# P-LED-0005-V1A_EAGLE_Schematic.net
KiCad netlist of a schematic drawn in EAGLE
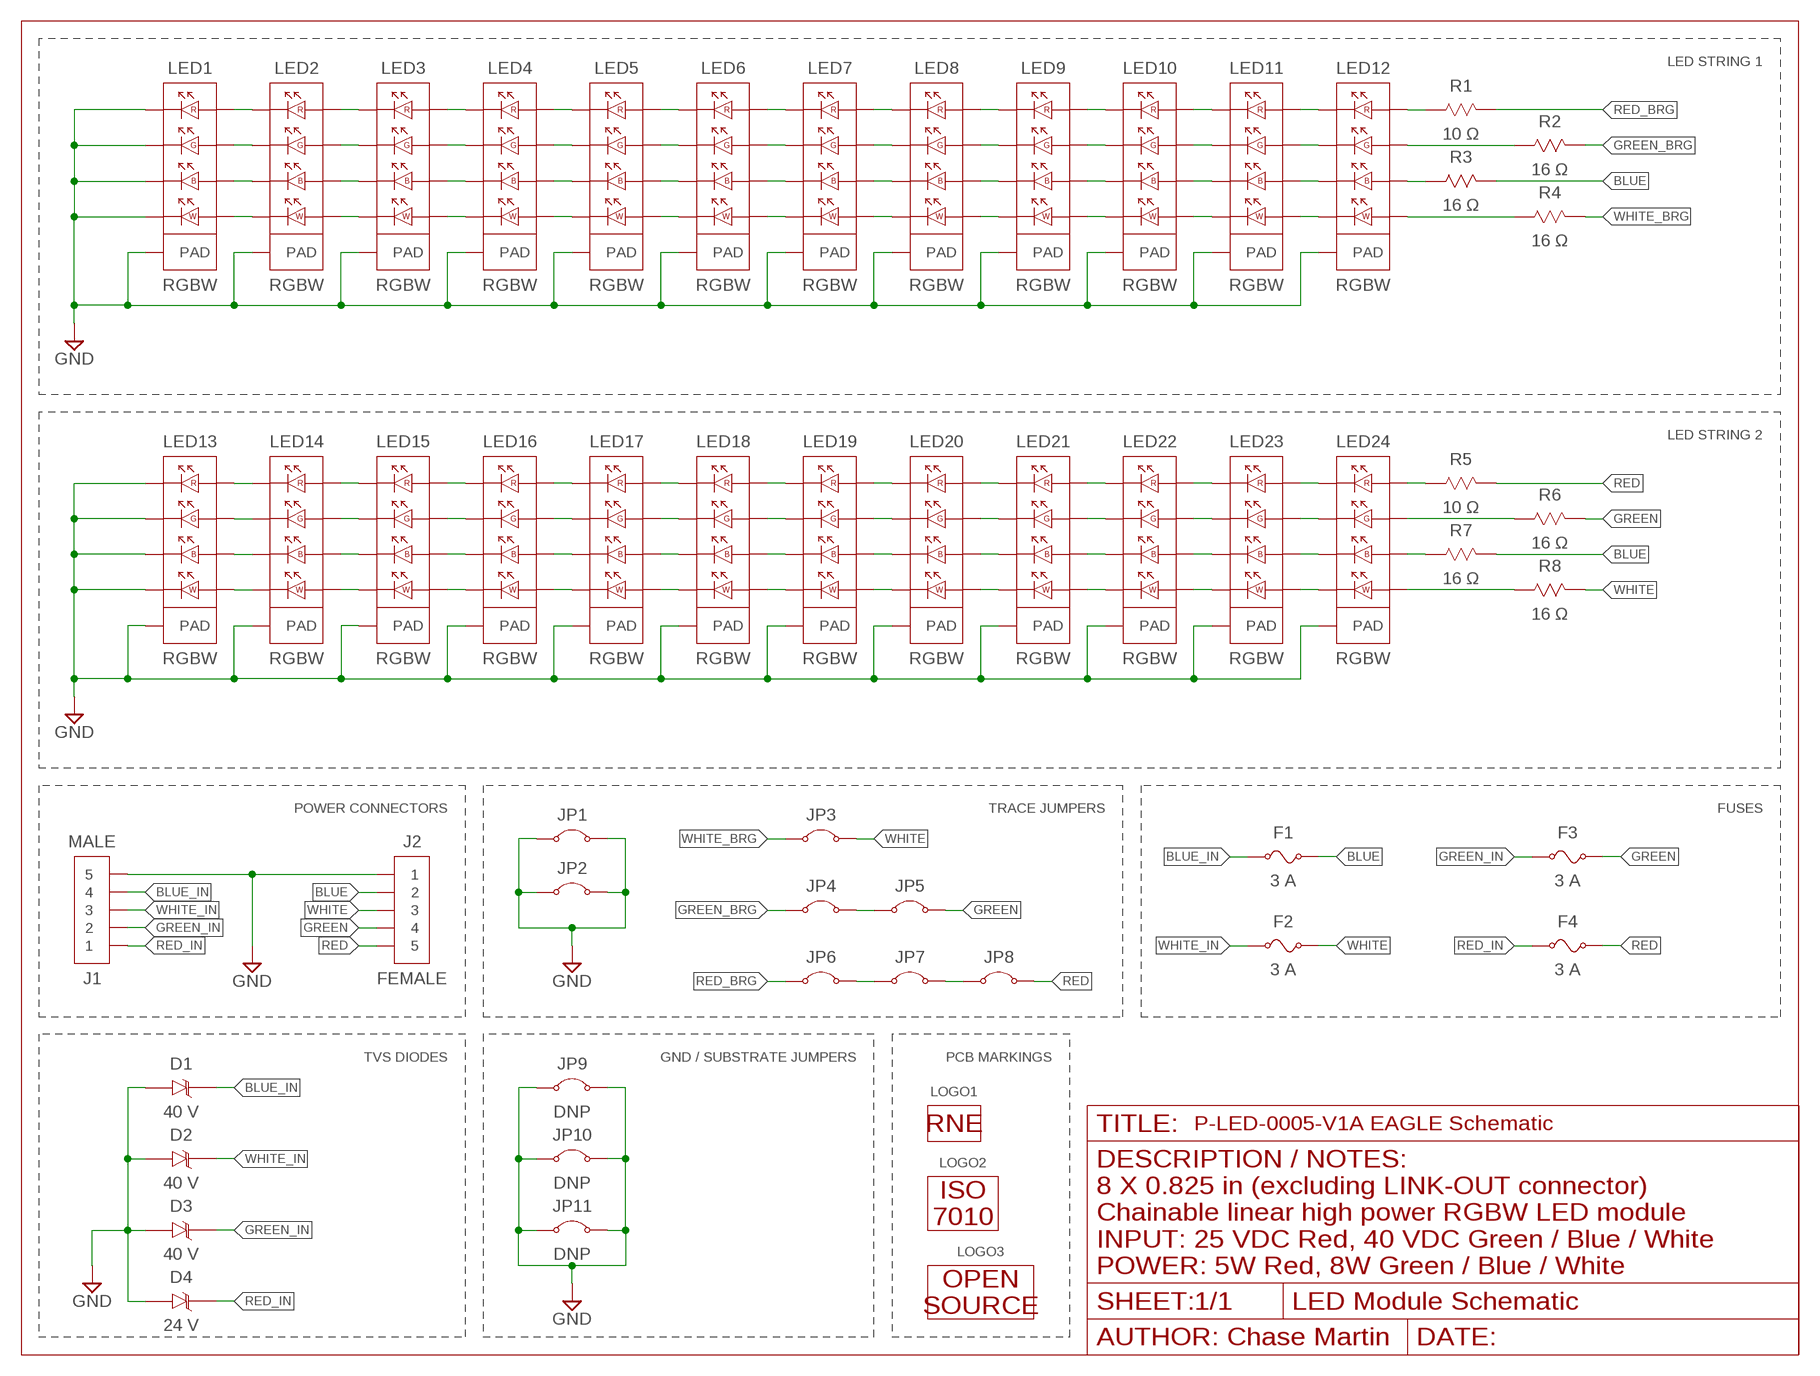
[diagram p0: schematic, sheet 1]

(export (version "E")
  (design (tool "Eeschema 10.0.6"))
  (components
    (comp (ref "D1")
      (value "40 V")
      (footprint "eagle-import:0603_POLARIZED")
      (libsource (lib "eagle-import") (part "UNIDIRECTIONAL_TVS_DIODESMD_0603"))
    )
    (comp (ref "D2")
      (value "40 V")
      (footprint "eagle-import:0603_POLARIZED")
      (libsource (lib "eagle-import") (part "UNIDIRECTIONAL_TVS_DIODESMD_0603"))
    )
    (comp (ref "D3")
      (value "40 V")
      (footprint "eagle-import:0603_POLARIZED")
      (libsource (lib "eagle-import") (part "UNIDIRECTIONAL_TVS_DIODESMD_0603"))
    )
    (comp (ref "D4")
      (value "24 V")
      (footprint "eagle-import:0603_POLARIZED")
      (libsource (lib "eagle-import") (part "UNIDIRECTIONAL_TVS_DIODESMD_0603"))
    )
    (comp (ref "F1")
      (value "3 A")
      (footprint "eagle-import:1206")
      (libsource (lib "eagle-import") (part "FUSESMD_1206"))
    )
    (comp (ref "F2")
      (value "3 A")
      (footprint "eagle-import:1206")
      (libsource (lib "eagle-import") (part "FUSESMD_1206"))
    )
    (comp (ref "F3")
      (value "3 A")
      (footprint "eagle-import:1206")
      (libsource (lib "eagle-import") (part "FUSESMD_1206"))
    )
    (comp (ref "F4")
      (value "3 A")
      (footprint "eagle-import:1206")
      (libsource (lib "eagle-import") (part "FUSESMD_1206"))
    )
    (comp (ref "J1")
      (value "MALE")
      (footprint "eagle-import:5-PIN_1-ROW_MALE_SMD_HORIZONTAL")
      (libsource (lib "eagle-import") (part "5-PIN_1-ROWMALE_SMD_HORIZONTAL"))
    )
    (comp (ref "J2")
      (value "FEMALE")
      (footprint "eagle-import:5-PIN_1-ROW_FEMALE_SMD_HORIZONTAL")
      (libsource (lib "eagle-import") (part "5-PIN_1-ROWFEMALE_SMD_HORIZONTAL"))
    )
    (comp (ref "JP1")
      (value "JUMPERSMD_1206")
      (footprint "eagle-import:1206")
      (libsource (lib "eagle-import") (part "JUMPERSMD_1206"))
    )
    (comp (ref "JP2")
      (value "JUMPERSMD_1206")
      (footprint "eagle-import:1206")
      (libsource (lib "eagle-import") (part "JUMPERSMD_1206"))
    )
    (comp (ref "JP3")
      (value "JUMPERSMD_1206")
      (footprint "eagle-import:1206")
      (libsource (lib "eagle-import") (part "JUMPERSMD_1206"))
    )
    (comp (ref "JP4")
      (value "JUMPERSMD_1206")
      (footprint "eagle-import:1206")
      (libsource (lib "eagle-import") (part "JUMPERSMD_1206"))
    )
    (comp (ref "JP5")
      (value "JUMPERSMD_1206")
      (footprint "eagle-import:1206")
      (libsource (lib "eagle-import") (part "JUMPERSMD_1206"))
    )
    (comp (ref "JP6")
      (value "JUMPERSMD_1206")
      (footprint "eagle-import:1206")
      (libsource (lib "eagle-import") (part "JUMPERSMD_1206"))
    )
    (comp (ref "JP7")
      (value "JUMPERSMD_1206")
      (footprint "eagle-import:1206")
      (libsource (lib "eagle-import") (part "JUMPERSMD_1206"))
    )
    (comp (ref "JP8")
      (value "JUMPERSMD_1206")
      (footprint "eagle-import:1206")
      (libsource (lib "eagle-import") (part "JUMPERSMD_1206"))
    )
    (comp (ref "JP9")
      (value "DNP")
      (footprint "eagle-import:0603")
      (libsource (lib "eagle-import") (part "JUMPERSMD_0603"))
    )
    (comp (ref "JP10")
      (value "DNP")
      (footprint "eagle-import:0603")
      (libsource (lib "eagle-import") (part "JUMPERSMD_0603"))
    )
    (comp (ref "JP11")
      (value "DNP")
      (footprint "eagle-import:0603")
      (libsource (lib "eagle-import") (part "JUMPERSMD_0603"))
    )
    (comp (ref "LED1")
      (value "RGBW")
      (footprint "eagle-import:IN-P55QSTGRGBW_FR4")
      (libsource (lib "eagle-import") (part "IN-P55QSTGRGBWFR4"))
    )
    (comp (ref "LED2")
      (value "RGBW")
      (footprint "eagle-import:IN-P55QSTGRGBW_FR4")
      (libsource (lib "eagle-import") (part "IN-P55QSTGRGBWFR4"))
    )
    (comp (ref "LED3")
      (value "RGBW")
      (footprint "eagle-import:IN-P55QSTGRGBW_FR4")
      (libsource (lib "eagle-import") (part "IN-P55QSTGRGBWFR4"))
    )
    (comp (ref "LED4")
      (value "RGBW")
      (footprint "eagle-import:IN-P55QSTGRGBW_FR4")
      (libsource (lib "eagle-import") (part "IN-P55QSTGRGBWFR4"))
    )
    (comp (ref "LED5")
      (value "RGBW")
      (footprint "eagle-import:IN-P55QSTGRGBW_FR4")
      (libsource (lib "eagle-import") (part "IN-P55QSTGRGBWFR4"))
    )
    (comp (ref "LED6")
      (value "RGBW")
      (footprint "eagle-import:IN-P55QSTGRGBW_FR4")
      (libsource (lib "eagle-import") (part "IN-P55QSTGRGBWFR4"))
    )
    (comp (ref "LED7")
      (value "RGBW")
      (footprint "eagle-import:IN-P55QSTGRGBW_FR4")
      (libsource (lib "eagle-import") (part "IN-P55QSTGRGBWFR4"))
    )
    (comp (ref "LED8")
      (value "RGBW")
      (footprint "eagle-import:IN-P55QSTGRGBW_FR4")
      (libsource (lib "eagle-import") (part "IN-P55QSTGRGBWFR4"))
    )
    (comp (ref "LED9")
      (value "RGBW")
      (footprint "eagle-import:IN-P55QSTGRGBW_FR4")
      (libsource (lib "eagle-import") (part "IN-P55QSTGRGBWFR4"))
    )
    (comp (ref "LED10")
      (value "RGBW")
      (footprint "eagle-import:IN-P55QSTGRGBW_FR4")
      (libsource (lib "eagle-import") (part "IN-P55QSTGRGBWFR4"))
    )
    (comp (ref "LED11")
      (value "RGBW")
      (footprint "eagle-import:IN-P55QSTGRGBW_FR4")
      (libsource (lib "eagle-import") (part "IN-P55QSTGRGBWFR4"))
    )
    (comp (ref "LED12")
      (value "RGBW")
      (footprint "eagle-import:IN-P55QSTGRGBW_FR4")
      (libsource (lib "eagle-import") (part "IN-P55QSTGRGBWFR4"))
    )
    (comp (ref "LED13")
      (value "RGBW")
      (footprint "eagle-import:IN-P55QSTGRGBW_FR4")
      (libsource (lib "eagle-import") (part "IN-P55QSTGRGBWFR4"))
    )
    (comp (ref "LED14")
      (value "RGBW")
      (footprint "eagle-import:IN-P55QSTGRGBW_FR4")
      (libsource (lib "eagle-import") (part "IN-P55QSTGRGBWFR4"))
    )
    (comp (ref "LED15")
      (value "RGBW")
      (footprint "eagle-import:IN-P55QSTGRGBW_FR4")
      (libsource (lib "eagle-import") (part "IN-P55QSTGRGBWFR4"))
    )
    (comp (ref "LED16")
      (value "RGBW")
      (footprint "eagle-import:IN-P55QSTGRGBW_FR4")
      (libsource (lib "eagle-import") (part "IN-P55QSTGRGBWFR4"))
    )
    (comp (ref "LED17")
      (value "RGBW")
      (footprint "eagle-import:IN-P55QSTGRGBW_FR4")
      (libsource (lib "eagle-import") (part "IN-P55QSTGRGBWFR4"))
    )
    (comp (ref "LED18")
      (value "RGBW")
      (footprint "eagle-import:IN-P55QSTGRGBW_FR4")
      (libsource (lib "eagle-import") (part "IN-P55QSTGRGBWFR4"))
    )
    (comp (ref "LED19")
      (value "RGBW")
      (footprint "eagle-import:IN-P55QSTGRGBW_FR4")
      (libsource (lib "eagle-import") (part "IN-P55QSTGRGBWFR4"))
    )
    (comp (ref "LED20")
      (value "RGBW")
      (footprint "eagle-import:IN-P55QSTGRGBW_FR4")
      (libsource (lib "eagle-import") (part "IN-P55QSTGRGBWFR4"))
    )
    (comp (ref "LED21")
      (value "RGBW")
      (footprint "eagle-import:IN-P55QSTGRGBW_FR4")
      (libsource (lib "eagle-import") (part "IN-P55QSTGRGBWFR4"))
    )
    (comp (ref "LED22")
      (value "RGBW")
      (footprint "eagle-import:IN-P55QSTGRGBW_FR4")
      (libsource (lib "eagle-import") (part "IN-P55QSTGRGBWFR4"))
    )
    (comp (ref "LED23")
      (value "RGBW")
      (footprint "eagle-import:IN-P55QSTGRGBW_FR4")
      (libsource (lib "eagle-import") (part "IN-P55QSTGRGBWFR4"))
    )
    (comp (ref "LED24")
      (value "RGBW")
      (footprint "eagle-import:IN-P55QSTGRGBW_FR4")
      (libsource (lib "eagle-import") (part "IN-P55QSTGRGBWFR4"))
    )
    (comp (ref "LOGO1")
      (value "PROFILE_LOGO_RNE0.375\"")
      (footprint "eagle-import:RNE_PROFILE-LOGO_375")
      (libsource (lib "eagle-import") (part "PROFILE_LOGO_RNE0.375{dblquote}"))
    )
    (comp (ref "LOGO2")
      (value "HOT_SURFACE_ISO0.375\"_LABEL")
      (footprint "eagle-import:ISO_HOT-SURFACE_375_LABEL")
      (libsource (lib "eagle-import") (part "HOT_SURFACE_ISO0.375{dblquote}_LABEL"))
    )
    (comp (ref "LOGO3")
      (value "OPEN_SOURCE_OSHWA0.375\"_LABEL")
      (footprint "eagle-import:OSHWA_OPEN-SOURCE_375_LABEL")
      (libsource (lib "eagle-import") (part "OPEN_SOURCE_OSHWA0.375{dblquote}_LABEL"))
    )
    (comp (ref "R1")
      (value "10 Ω")
      (footprint "eagle-import:0603")
      (libsource (lib "eagle-import") (part "RESISTORSMD_0603"))
    )
    (comp (ref "R2")
      (value "16 Ω")
      (footprint "eagle-import:0603")
      (libsource (lib "eagle-import") (part "RESISTORSMD_0603"))
    )
    (comp (ref "R3")
      (value "16 Ω")
      (footprint "eagle-import:0603")
      (libsource (lib "eagle-import") (part "RESISTORSMD_0603"))
    )
    (comp (ref "R4")
      (value "16 Ω")
      (footprint "eagle-import:0603")
      (libsource (lib "eagle-import") (part "RESISTORSMD_0603"))
    )
    (comp (ref "R5")
      (value "10 Ω")
      (footprint "eagle-import:0603")
      (libsource (lib "eagle-import") (part "RESISTORSMD_0603"))
    )
    (comp (ref "R6")
      (value "16 Ω")
      (footprint "eagle-import:0603")
      (libsource (lib "eagle-import") (part "RESISTORSMD_0603"))
    )
    (comp (ref "R7")
      (value "16 Ω")
      (footprint "eagle-import:0603")
      (libsource (lib "eagle-import") (part "RESISTORSMD_0603"))
    )
    (comp (ref "R8")
      (value "16 Ω")
      (footprint "eagle-import:0603")
      (libsource (lib "eagle-import") (part "RESISTORSMD_0603"))
    )
  )
  (nets
    (net (code "1") (name "BLUE") (class "Default")
      (node (ref "F1") (pin "2") (pinfunction "2_2") (pintype "passive"))
      (node (ref "J2") (pin "2") (pinfunction "2_2") (pintype "passive"))
      (node (ref "R3") (pin "2") (pinfunction "2_2") (pintype "passive"))
      (node (ref "R7") (pin "2") (pinfunction "2_2") (pintype "passive"))
    )
    (net (code "2") (name "BLUE_IN") (class "Default")
      (node (ref "D1") (pin "K") (pinfunction "K_K") (pintype "passive"))
      (node (ref "F1") (pin "1") (pinfunction "1_1") (pintype "passive"))
      (node (ref "J1") (pin "4") (pinfunction "4_4") (pintype "passive"))
    )
    (net (code "3") (name "GND") (class "Default")
      (node (ref "D1") (pin "A") (pinfunction "A_A") (pintype "passive"))
      (node (ref "D2") (pin "A") (pinfunction "A_A") (pintype "passive"))
      (node (ref "D3") (pin "A") (pinfunction "A_A") (pintype "passive"))
      (node (ref "D4") (pin "A") (pinfunction "A_A") (pintype "passive"))
      (node (ref "J1") (pin "5") (pinfunction "5_5") (pintype "passive"))
      (node (ref "J2") (pin "1") (pinfunction "1_1") (pintype "passive"))
      (node (ref "JP1") (pin "1") (pinfunction "1_1") (pintype "passive"))
      (node (ref "JP1") (pin "2") (pinfunction "2_2") (pintype "passive"))
      (node (ref "JP10") (pin "1") (pinfunction "1_1") (pintype "passive"))
      (node (ref "JP10") (pin "2") (pinfunction "2_2") (pintype "passive"))
      (node (ref "JP11") (pin "1") (pinfunction "1_1") (pintype "passive"))
      (node (ref "JP11") (pin "2") (pinfunction "2_2") (pintype "passive"))
      (node (ref "JP2") (pin "1") (pinfunction "1_1") (pintype "passive"))
      (node (ref "JP2") (pin "2") (pinfunction "2_2") (pintype "passive"))
      (node (ref "JP9") (pin "1") (pinfunction "1_1") (pintype "passive"))
      (node (ref "JP9") (pin "2") (pinfunction "2_2") (pintype "passive"))
      (node (ref "LED1") (pin "BLUE_N") (pinfunction "BLUE_N_BLUE_N") (pintype "output"))
      (node (ref "LED1") (pin "GREEN_N") (pinfunction "GREEN_N_GREEN_N") (pintype "output"))
      (node (ref "LED1") (pin "PAD_B") (pinfunction "PAD_PAD_B") (pintype "passive"))
      (node (ref "LED1") (pin "PAD_T") (pinfunction "PAD_PAD_T") (pintype "passive"))
      (node (ref "LED1") (pin "RED_N") (pinfunction "RED_N_RED_N") (pintype "output"))
      (node (ref "LED1") (pin "VIA1") (pinfunction "PAD_VIA1") (pintype "passive"))
      (node (ref "LED1") (pin "VIA10") (pinfunction "PAD_VIA10") (pintype "passive"))
      (node (ref "LED1") (pin "VIA11") (pinfunction "PAD_VIA11") (pintype "passive"))
      (node (ref "LED1") (pin "VIA12") (pinfunction "PAD_VIA12") (pintype "passive"))
      (node (ref "LED1") (pin "VIA2") (pinfunction "PAD_VIA2") (pintype "passive"))
      (node (ref "LED1") (pin "VIA3") (pinfunction "PAD_VIA3") (pintype "passive"))
      (node (ref "LED1") (pin "VIA4") (pinfunction "PAD_VIA4") (pintype "passive"))
      (node (ref "LED1") (pin "VIA5") (pinfunction "PAD_VIA5") (pintype "passive"))
      (node (ref "LED1") (pin "VIA6") (pinfunction "PAD_VIA6") (pintype "passive"))
      (node (ref "LED1") (pin "VIA7") (pinfunction "PAD_VIA7") (pintype "passive"))
      (node (ref "LED1") (pin "VIA8") (pinfunction "PAD_VIA8") (pintype "passive"))
      (node (ref "LED1") (pin "VIA9") (pinfunction "PAD_VIA9") (pintype "passive"))
      (node (ref "LED1") (pin "WHITE_N") (pinfunction "WHITE_N_WHITE_N") (pintype "output"))
      (node (ref "LED10") (pin "PAD_B") (pinfunction "PAD_PAD_B") (pintype "passive"))
      (node (ref "LED10") (pin "PAD_T") (pinfunction "PAD_PAD_T") (pintype "passive"))
      (node (ref "LED10") (pin "VIA1") (pinfunction "PAD_VIA1") (pintype "passive"))
      (node (ref "LED10") (pin "VIA10") (pinfunction "PAD_VIA10") (pintype "passive"))
      (node (ref "LED10") (pin "VIA11") (pinfunction "PAD_VIA11") (pintype "passive"))
      (node (ref "LED10") (pin "VIA12") (pinfunction "PAD_VIA12") (pintype "passive"))
      (node (ref "LED10") (pin "VIA2") (pinfunction "PAD_VIA2") (pintype "passive"))
      (node (ref "LED10") (pin "VIA3") (pinfunction "PAD_VIA3") (pintype "passive"))
      (node (ref "LED10") (pin "VIA4") (pinfunction "PAD_VIA4") (pintype "passive"))
      (node (ref "LED10") (pin "VIA5") (pinfunction "PAD_VIA5") (pintype "passive"))
      (node (ref "LED10") (pin "VIA6") (pinfunction "PAD_VIA6") (pintype "passive"))
      (node (ref "LED10") (pin "VIA7") (pinfunction "PAD_VIA7") (pintype "passive"))
      (node (ref "LED10") (pin "VIA8") (pinfunction "PAD_VIA8") (pintype "passive"))
      (node (ref "LED10") (pin "VIA9") (pinfunction "PAD_VIA9") (pintype "passive"))
      (node (ref "LED11") (pin "PAD_B") (pinfunction "PAD_PAD_B") (pintype "passive"))
      (node (ref "LED11") (pin "PAD_T") (pinfunction "PAD_PAD_T") (pintype "passive"))
      (node (ref "LED11") (pin "VIA1") (pinfunction "PAD_VIA1") (pintype "passive"))
      (node (ref "LED11") (pin "VIA10") (pinfunction "PAD_VIA10") (pintype "passive"))
      (node (ref "LED11") (pin "VIA11") (pinfunction "PAD_VIA11") (pintype "passive"))
      (node (ref "LED11") (pin "VIA12") (pinfunction "PAD_VIA12") (pintype "passive"))
      (node (ref "LED11") (pin "VIA2") (pinfunction "PAD_VIA2") (pintype "passive"))
      (node (ref "LED11") (pin "VIA3") (pinfunction "PAD_VIA3") (pintype "passive"))
      (node (ref "LED11") (pin "VIA4") (pinfunction "PAD_VIA4") (pintype "passive"))
      (node (ref "LED11") (pin "VIA5") (pinfunction "PAD_VIA5") (pintype "passive"))
      (node (ref "LED11") (pin "VIA6") (pinfunction "PAD_VIA6") (pintype "passive"))
      (node (ref "LED11") (pin "VIA7") (pinfunction "PAD_VIA7") (pintype "passive"))
      (node (ref "LED11") (pin "VIA8") (pinfunction "PAD_VIA8") (pintype "passive"))
      (node (ref "LED11") (pin "VIA9") (pinfunction "PAD_VIA9") (pintype "passive"))
      (node (ref "LED12") (pin "PAD_B") (pinfunction "PAD_PAD_B") (pintype "passive"))
      (node (ref "LED12") (pin "PAD_T") (pinfunction "PAD_PAD_T") (pintype "passive"))
      (node (ref "LED12") (pin "VIA1") (pinfunction "PAD_VIA1") (pintype "passive"))
      (node (ref "LED12") (pin "VIA10") (pinfunction "PAD_VIA10") (pintype "passive"))
      (node (ref "LED12") (pin "VIA11") (pinfunction "PAD_VIA11") (pintype "passive"))
      (node (ref "LED12") (pin "VIA12") (pinfunction "PAD_VIA12") (pintype "passive"))
      (node (ref "LED12") (pin "VIA2") (pinfunction "PAD_VIA2") (pintype "passive"))
      (node (ref "LED12") (pin "VIA3") (pinfunction "PAD_VIA3") (pintype "passive"))
      (node (ref "LED12") (pin "VIA4") (pinfunction "PAD_VIA4") (pintype "passive"))
      (node (ref "LED12") (pin "VIA5") (pinfunction "PAD_VIA5") (pintype "passive"))
      (node (ref "LED12") (pin "VIA6") (pinfunction "PAD_VIA6") (pintype "passive"))
      (node (ref "LED12") (pin "VIA7") (pinfunction "PAD_VIA7") (pintype "passive"))
      (node (ref "LED12") (pin "VIA8") (pinfunction "PAD_VIA8") (pintype "passive"))
      (node (ref "LED12") (pin "VIA9") (pinfunction "PAD_VIA9") (pintype "passive"))
      (node (ref "LED13") (pin "BLUE_N") (pinfunction "BLUE_N_BLUE_N") (pintype "output"))
      (node (ref "LED13") (pin "GREEN_N") (pinfunction "GREEN_N_GREEN_N") (pintype "output"))
      (node (ref "LED13") (pin "PAD_B") (pinfunction "PAD_PAD_B") (pintype "passive"))
      (node (ref "LED13") (pin "PAD_T") (pinfunction "PAD_PAD_T") (pintype "passive"))
      (node (ref "LED13") (pin "RED_N") (pinfunction "RED_N_RED_N") (pintype "output"))
      (node (ref "LED13") (pin "VIA1") (pinfunction "PAD_VIA1") (pintype "passive"))
      (node (ref "LED13") (pin "VIA10") (pinfunction "PAD_VIA10") (pintype "passive"))
      (node (ref "LED13") (pin "VIA11") (pinfunction "PAD_VIA11") (pintype "passive"))
      (node (ref "LED13") (pin "VIA12") (pinfunction "PAD_VIA12") (pintype "passive"))
      (node (ref "LED13") (pin "VIA2") (pinfunction "PAD_VIA2") (pintype "passive"))
      (node (ref "LED13") (pin "VIA3") (pinfunction "PAD_VIA3") (pintype "passive"))
      (node (ref "LED13") (pin "VIA4") (pinfunction "PAD_VIA4") (pintype "passive"))
      (node (ref "LED13") (pin "VIA5") (pinfunction "PAD_VIA5") (pintype "passive"))
      (node (ref "LED13") (pin "VIA6") (pinfunction "PAD_VIA6") (pintype "passive"))
      (node (ref "LED13") (pin "VIA7") (pinfunction "PAD_VIA7") (pintype "passive"))
      (node (ref "LED13") (pin "VIA8") (pinfunction "PAD_VIA8") (pintype "passive"))
      (node (ref "LED13") (pin "VIA9") (pinfunction "PAD_VIA9") (pintype "passive"))
      (node (ref "LED13") (pin "WHITE_N") (pinfunction "WHITE_N_WHITE_N") (pintype "output"))
      (node (ref "LED14") (pin "PAD_B") (pinfunction "PAD_PAD_B") (pintype "passive"))
      (node (ref "LED14") (pin "PAD_T") (pinfunction "PAD_PAD_T") (pintype "passive"))
      (node (ref "LED14") (pin "VIA1") (pinfunction "PAD_VIA1") (pintype "passive"))
      (node (ref "LED14") (pin "VIA10") (pinfunction "PAD_VIA10") (pintype "passive"))
      (node (ref "LED14") (pin "VIA11") (pinfunction "PAD_VIA11") (pintype "passive"))
      (node (ref "LED14") (pin "VIA12") (pinfunction "PAD_VIA12") (pintype "passive"))
      (node (ref "LED14") (pin "VIA2") (pinfunction "PAD_VIA2") (pintype "passive"))
      (node (ref "LED14") (pin "VIA3") (pinfunction "PAD_VIA3") (pintype "passive"))
      (node (ref "LED14") (pin "VIA4") (pinfunction "PAD_VIA4") (pintype "passive"))
      (node (ref "LED14") (pin "VIA5") (pinfunction "PAD_VIA5") (pintype "passive"))
      (node (ref "LED14") (pin "VIA6") (pinfunction "PAD_VIA6") (pintype "passive"))
      (node (ref "LED14") (pin "VIA7") (pinfunction "PAD_VIA7") (pintype "passive"))
      (node (ref "LED14") (pin "VIA8") (pinfunction "PAD_VIA8") (pintype "passive"))
      (node (ref "LED14") (pin "VIA9") (pinfunction "PAD_VIA9") (pintype "passive"))
      (node (ref "LED15") (pin "PAD_B") (pinfunction "PAD_PAD_B") (pintype "passive"))
      (node (ref "LED15") (pin "PAD_T") (pinfunction "PAD_PAD_T") (pintype "passive"))
      (node (ref "LED15") (pin "VIA1") (pinfunction "PAD_VIA1") (pintype "passive"))
      (node (ref "LED15") (pin "VIA10") (pinfunction "PAD_VIA10") (pintype "passive"))
      (node (ref "LED15") (pin "VIA11") (pinfunction "PAD_VIA11") (pintype "passive"))
      (node (ref "LED15") (pin "VIA12") (pinfunction "PAD_VIA12") (pintype "passive"))
      (node (ref "LED15") (pin "VIA2") (pinfunction "PAD_VIA2") (pintype "passive"))
      (node (ref "LED15") (pin "VIA3") (pinfunction "PAD_VIA3") (pintype "passive"))
      (node (ref "LED15") (pin "VIA4") (pinfunction "PAD_VIA4") (pintype "passive"))
      (node (ref "LED15") (pin "VIA5") (pinfunction "PAD_VIA5") (pintype "passive"))
      (node (ref "LED15") (pin "VIA6") (pinfunction "PAD_VIA6") (pintype "passive"))
      (node (ref "LED15") (pin "VIA7") (pinfunction "PAD_VIA7") (pintype "passive"))
      (node (ref "LED15") (pin "VIA8") (pinfunction "PAD_VIA8") (pintype "passive"))
      (node (ref "LED15") (pin "VIA9") (pinfunction "PAD_VIA9") (pintype "passive"))
      (node (ref "LED16") (pin "PAD_B") (pinfunction "PAD_PAD_B") (pintype "passive"))
      (node (ref "LED16") (pin "PAD_T") (pinfunction "PAD_PAD_T") (pintype "passive"))
      (node (ref "LED16") (pin "VIA1") (pinfunction "PAD_VIA1") (pintype "passive"))
      (node (ref "LED16") (pin "VIA10") (pinfunction "PAD_VIA10") (pintype "passive"))
      (node (ref "LED16") (pin "VIA11") (pinfunction "PAD_VIA11") (pintype "passive"))
      (node (ref "LED16") (pin "VIA12") (pinfunction "PAD_VIA12") (pintype "passive"))
      (node (ref "LED16") (pin "VIA2") (pinfunction "PAD_VIA2") (pintype "passive"))
      (node (ref "LED16") (pin "VIA3") (pinfunction "PAD_VIA3") (pintype "passive"))
      (node (ref "LED16") (pin "VIA4") (pinfunction "PAD_VIA4") (pintype "passive"))
      (node (ref "LED16") (pin "VIA5") (pinfunction "PAD_VIA5") (pintype "passive"))
      (node (ref "LED16") (pin "VIA6") (pinfunction "PAD_VIA6") (pintype "passive"))
      (node (ref "LED16") (pin "VIA7") (pinfunction "PAD_VIA7") (pintype "passive"))
      (node (ref "LED16") (pin "VIA8") (pinfunction "PAD_VIA8") (pintype "passive"))
      (node (ref "LED16") (pin "VIA9") (pinfunction "PAD_VIA9") (pintype "passive"))
      (node (ref "LED17") (pin "PAD_B") (pinfunction "PAD_PAD_B") (pintype "passive"))
      (node (ref "LED17") (pin "PAD_T") (pinfunction "PAD_PAD_T") (pintype "passive"))
      (node (ref "LED17") (pin "VIA1") (pinfunction "PAD_VIA1") (pintype "passive"))
      (node (ref "LED17") (pin "VIA10") (pinfunction "PAD_VIA10") (pintype "passive"))
      (node (ref "LED17") (pin "VIA11") (pinfunction "PAD_VIA11") (pintype "passive"))
      (node (ref "LED17") (pin "VIA12") (pinfunction "PAD_VIA12") (pintype "passive"))
      (node (ref "LED17") (pin "VIA2") (pinfunction "PAD_VIA2") (pintype "passive"))
      (node (ref "LED17") (pin "VIA3") (pinfunction "PAD_VIA3") (pintype "passive"))
      (node (ref "LED17") (pin "VIA4") (pinfunction "PAD_VIA4") (pintype "passive"))
      (node (ref "LED17") (pin "VIA5") (pinfunction "PAD_VIA5") (pintype "passive"))
      (node (ref "LED17") (pin "VIA6") (pinfunction "PAD_VIA6") (pintype "passive"))
      (node (ref "LED17") (pin "VIA7") (pinfunction "PAD_VIA7") (pintype "passive"))
      (node (ref "LED17") (pin "VIA8") (pinfunction "PAD_VIA8") (pintype "passive"))
      (node (ref "LED17") (pin "VIA9") (pinfunction "PAD_VIA9") (pintype "passive"))
      (node (ref "LED18") (pin "PAD_B") (pinfunction "PAD_PAD_B") (pintype "passive"))
      (node (ref "LED18") (pin "PAD_T") (pinfunction "PAD_PAD_T") (pintype "passive"))
      (node (ref "LED18") (pin "VIA1") (pinfunction "PAD_VIA1") (pintype "passive"))
      (node (ref "LED18") (pin "VIA10") (pinfunction "PAD_VIA10") (pintype "passive"))
      (node (ref "LED18") (pin "VIA11") (pinfunction "PAD_VIA11") (pintype "passive"))
      (node (ref "LED18") (pin "VIA12") (pinfunction "PAD_VIA12") (pintype "passive"))
      (node (ref "LED18") (pin "VIA2") (pinfunction "PAD_VIA2") (pintype "passive"))
      (node (ref "LED18") (pin "VIA3") (pinfunction "PAD_VIA3") (pintype "passive"))
      (node (ref "LED18") (pin "VIA4") (pinfunction "PAD_VIA4") (pintype "passive"))
      (node (ref "LED18") (pin "VIA5") (pinfunction "PAD_VIA5") (pintype "passive"))
      (node (ref "LED18") (pin "VIA6") (pinfunction "PAD_VIA6") (pintype "passive"))
      (node (ref "LED18") (pin "VIA7") (pinfunction "PAD_VIA7") (pintype "passive"))
      (node (ref "LED18") (pin "VIA8") (pinfunction "PAD_VIA8") (pintype "passive"))
      (node (ref "LED18") (pin "VIA9") (pinfunction "PAD_VIA9") (pintype "passive"))
      (node (ref "LED19") (pin "PAD_B") (pinfunction "PAD_PAD_B") (pintype "passive"))
      (node (ref "LED19") (pin "PAD_T") (pinfunction "PAD_PAD_T") (pintype "passive"))
      (node (ref "LED19") (pin "VIA1") (pinfunction "PAD_VIA1") (pintype "passive"))
      (node (ref "LED19") (pin "VIA10") (pinfunction "PAD_VIA10") (pintype "passive"))
      (node (ref "LED19") (pin "VIA11") (pinfunction "PAD_VIA11") (pintype "passive"))
      (node (ref "LED19") (pin "VIA12") (pinfunction "PAD_VIA12") (pintype "passive"))
      (node (ref "LED19") (pin "VIA2") (pinfunction "PAD_VIA2") (pintype "passive"))
      (node (ref "LED19") (pin "VIA3") (pinfunction "PAD_VIA3") (pintype "passive"))
      (node (ref "LED19") (pin "VIA4") (pinfunction "PAD_VIA4") (pintype "passive"))
      (node (ref "LED19") (pin "VIA5") (pinfunction "PAD_VIA5") (pintype "passive"))
      (node (ref "LED19") (pin "VIA6") (pinfunction "PAD_VIA6") (pintype "passive"))
      (node (ref "LED19") (pin "VIA7") (pinfunction "PAD_VIA7") (pintype "passive"))
      (node (ref "LED19") (pin "VIA8") (pinfunction "PAD_VIA8") (pintype "passive"))
      (node (ref "LED19") (pin "VIA9") (pinfunction "PAD_VIA9") (pintype "passive"))
      (node (ref "LED2") (pin "PAD_B") (pinfunction "PAD_PAD_B") (pintype "passive"))
      (node (ref "LED2") (pin "PAD_T") (pinfunction "PAD_PAD_T") (pintype "passive"))
      (node (ref "LED2") (pin "VIA1") (pinfunction "PAD_VIA1") (pintype "passive"))
      (node (ref "LED2") (pin "VIA10") (pinfunction "PAD_VIA10") (pintype "passive"))
      (node (ref "LED2") (pin "VIA11") (pinfunction "PAD_VIA11") (pintype "passive"))
      (node (ref "LED2") (pin "VIA12") (pinfunction "PAD_VIA12") (pintype "passive"))
      (node (ref "LED2") (pin "VIA2") (pinfunction "PAD_VIA2") (pintype "passive"))
      (node (ref "LED2") (pin "VIA3") (pinfunction "PAD_VIA3") (pintype "passive"))
      (node (ref "LED2") (pin "VIA4") (pinfunction "PAD_VIA4") (pintype "passive"))
      (node (ref "LED2") (pin "VIA5") (pinfunction "PAD_VIA5") (pintype "passive"))
      (node (ref "LED2") (pin "VIA6") (pinfunction "PAD_VIA6") (pintype "passive"))
      (node (ref "LED2") (pin "VIA7") (pinfunction "PAD_VIA7") (pintype "passive"))
      (node (ref "LED2") (pin "VIA8") (pinfunction "PAD_VIA8") (pintype "passive"))
      (node (ref "LED2") (pin "VIA9") (pinfunction "PAD_VIA9") (pintype "passive"))
      (node (ref "LED20") (pin "PAD_B") (pinfunction "PAD_PAD_B") (pintype "passive"))
      (node (ref "LED20") (pin "PAD_T") (pinfunction "PAD_PAD_T") (pintype "passive"))
      (node (ref "LED20") (pin "VIA1") (pinfunction "PAD_VIA1") (pintype "passive"))
      (node (ref "LED20") (pin "VIA10") (pinfunction "PAD_VIA10") (pintype "passive"))
      (node (ref "LED20") (pin "VIA11") (pinfunction "PAD_VIA11") (pintype "passive"))
      (node (ref "LED20") (pin "VIA12") (pinfunction "PAD_VIA12") (pintype "passive"))
      (node (ref "LED20") (pin "VIA2") (pinfunction "PAD_VIA2") (pintype "passive"))
      (node (ref "LED20") (pin "VIA3") (pinfunction "PAD_VIA3") (pintype "passive"))
      (node (ref "LED20") (pin "VIA4") (pinfunction "PAD_VIA4") (pintype "passive"))
      (node (ref "LED20") (pin "VIA5") (pinfunction "PAD_VIA5") (pintype "passive"))
      (node (ref "LED20") (pin "VIA6") (pinfunction "PAD_VIA6") (pintype "passive"))
      (node (ref "LED20") (pin "VIA7") (pinfunction "PAD_VIA7") (pintype "passive"))
      (node (ref "LED20") (pin "VIA8") (pinfunction "PAD_VIA8") (pintype "passive"))
      (node (ref "LED20") (pin "VIA9") (pinfunction "PAD_VIA9") (pintype "passive"))
      (node (ref "LED21") (pin "PAD_B") (pinfunction "PAD_PAD_B") (pintype "passive"))
      (node (ref "LED21") (pin "PAD_T") (pinfunction "PAD_PAD_T") (pintype "passive"))
      (node (ref "LED21") (pin "VIA1") (pinfunction "PAD_VIA1") (pintype "passive"))
      (node (ref "LED21") (pin "VIA10") (pinfunction "PAD_VIA10") (pintype "passive"))
      (node (ref "LED21") (pin "VIA11") (pinfunction "PAD_VIA11") (pintype "passive"))
      (node (ref "LED21") (pin "VIA12") (pinfunction "PAD_VIA12") (pintype "passive"))
      (node (ref "LED21") (pin "VIA2") (pinfunction "PAD_VIA2") (pintype "passive"))
      (node (ref "LED21") (pin "VIA3") (pinfunction "PAD_VIA3") (pintype "passive"))
      (node (ref "LED21") (pin "VIA4") (pinfunction "PAD_VIA4") (pintype "passive"))
      (node (ref "LED21") (pin "VIA5") (pinfunction "PAD_VIA5") (pintype "passive"))
      (node (ref "LED21") (pin "VIA6") (pinfunction "PAD_VIA6") (pintype "passive"))
      (node (ref "LED21") (pin "VIA7") (pinfunction "PAD_VIA7") (pintype "passive"))
      (node (ref "LED21") (pin "VIA8") (pinfunction "PAD_VIA8") (pintype "passive"))
      (node (ref "LED21") (pin "VIA9") (pinfunction "PAD_VIA9") (pintype "passive"))
      (node (ref "LED22") (pin "PAD_B") (pinfunction "PAD_PAD_B") (pintype "passive"))
      (node (ref "LED22") (pin "PAD_T") (pinfunction "PAD_PAD_T") (pintype "passive"))
      (node (ref "LED22") (pin "VIA1") (pinfunction "PAD_VIA1") (pintype "passive"))
      (node (ref "LED22") (pin "VIA10") (pinfunction "PAD_VIA10") (pintype "passive"))
      (node (ref "LED22") (pin "VIA11") (pinfunction "PAD_VIA11") (pintype "passive"))
      (node (ref "LED22") (pin "VIA12") (pinfunction "PAD_VIA12") (pintype "passive"))
      (node (ref "LED22") (pin "VIA2") (pinfunction "PAD_VIA2") (pintype "passive"))
      (node (ref "LED22") (pin "VIA3") (pinfunction "PAD_VIA3") (pintype "passive"))
      (node (ref "LED22") (pin "VIA4") (pinfunction "PAD_VIA4") (pintype "passive"))
      (node (ref "LED22") (pin "VIA5") (pinfunction "PAD_VIA5") (pintype "passive"))
      (node (ref "LED22") (pin "VIA6") (pinfunction "PAD_VIA6") (pintype "passive"))
      (node (ref "LED22") (pin "VIA7") (pinfunction "PAD_VIA7") (pintype "passive"))
      (node (ref "LED22") (pin "VIA8") (pinfunction "PAD_VIA8") (pintype "passive"))
      (node (ref "LED22") (pin "VIA9") (pinfunction "PAD_VIA9") (pintype "passive"))
      (node (ref "LED23") (pin "PAD_B") (pinfunction "PAD_PAD_B") (pintype "passive"))
      (node (ref "LED23") (pin "PAD_T") (pinfunction "PAD_PAD_T") (pintype "passive"))
      (node (ref "LED23") (pin "VIA1") (pinfunction "PAD_VIA1") (pintype "passive"))
      (node (ref "LED23") (pin "VIA10") (pinfunction "PAD_VIA10") (pintype "passive"))
      (node (ref "LED23") (pin "VIA11") (pinfunction "PAD_VIA11") (pintype "passive"))
      (node (ref "LED23") (pin "VIA12") (pinfunction "PAD_VIA12") (pintype "passive"))
      (node (ref "LED23") (pin "VIA2") (pinfunction "PAD_VIA2") (pintype "passive"))
      (node (ref "LED23") (pin "VIA3") (pinfunction "PAD_VIA3") (pintype "passive"))
      (node (ref "LED23") (pin "VIA4") (pinfunction "PAD_VIA4") (pintype "passive"))
      (node (ref "LED23") (pin "VIA5") (pinfunction "PAD_VIA5") (pintype "passive"))
      (node (ref "LED23") (pin "VIA6") (pinfunction "PAD_VIA6") (pintype "passive"))
      (node (ref "LED23") (pin "VIA7") (pinfunction "PAD_VIA7") (pintype "passive"))
      (node (ref "LED23") (pin "VIA8") (pinfunction "PAD_VIA8") (pintype "passive"))
      (node (ref "LED23") (pin "VIA9") (pinfunction "PAD_VIA9") (pintype "passive"))
      (node (ref "LED24") (pin "PAD_B") (pinfunction "PAD_PAD_B") (pintype "passive"))
      (node (ref "LED24") (pin "PAD_T") (pinfunction "PAD_PAD_T") (pintype "passive"))
      (node (ref "LED24") (pin "VIA1") (pinfunction "PAD_VIA1") (pintype "passive"))
      (node (ref "LED24") (pin "VIA10") (pinfunction "PAD_VIA10") (pintype "passive"))
      (node (ref "LED24") (pin "VIA11") (pinfunction "PAD_VIA11") (pintype "passive"))
      (node (ref "LED24") (pin "VIA12") (pinfunction "PAD_VIA12") (pintype "passive"))
      (node (ref "LED24") (pin "VIA2") (pinfunction "PAD_VIA2") (pintype "passive"))
      (node (ref "LED24") (pin "VIA3") (pinfunction "PAD_VIA3") (pintype "passive"))
      (node (ref "LED24") (pin "VIA4") (pinfunction "PAD_VIA4") (pintype "passive"))
      (node (ref "LED24") (pin "VIA5") (pinfunction "PAD_VIA5") (pintype "passive"))
      (node (ref "LED24") (pin "VIA6") (pinfunction "PAD_VIA6") (pintype "passive"))
      (node (ref "LED24") (pin "VIA7") (pinfunction "PAD_VIA7") (pintype "passive"))
      (node (ref "LED24") (pin "VIA8") (pinfunction "PAD_VIA8") (pintype "passive"))
      (node (ref "LED24") (pin "VIA9") (pinfunction "PAD_VIA9") (pintype "passive"))
      (node (ref "LED3") (pin "PAD_B") (pinfunction "PAD_PAD_B") (pintype "passive"))
      (node (ref "LED3") (pin "PAD_T") (pinfunction "PAD_PAD_T") (pintype "passive"))
      (node (ref "LED3") (pin "VIA1") (pinfunction "PAD_VIA1") (pintype "passive"))
      (node (ref "LED3") (pin "VIA10") (pinfunction "PAD_VIA10") (pintype "passive"))
      (node (ref "LED3") (pin "VIA11") (pinfunction "PAD_VIA11") (pintype "passive"))
      (node (ref "LED3") (pin "VIA12") (pinfunction "PAD_VIA12") (pintype "passive"))
      (node (ref "LED3") (pin "VIA2") (pinfunction "PAD_VIA2") (pintype "passive"))
      (node (ref "LED3") (pin "VIA3") (pinfunction "PAD_VIA3") (pintype "passive"))
      (node (ref "LED3") (pin "VIA4") (pinfunction "PAD_VIA4") (pintype "passive"))
      (node (ref "LED3") (pin "VIA5") (pinfunction "PAD_VIA5") (pintype "passive"))
      (node (ref "LED3") (pin "VIA6") (pinfunction "PAD_VIA6") (pintype "passive"))
      (node (ref "LED3") (pin "VIA7") (pinfunction "PAD_VIA7") (pintype "passive"))
      (node (ref "LED3") (pin "VIA8") (pinfunction "PAD_VIA8") (pintype "passive"))
      (node (ref "LED3") (pin "VIA9") (pinfunction "PAD_VIA9") (pintype "passive"))
      (node (ref "LED4") (pin "PAD_B") (pinfunction "PAD_PAD_B") (pintype "passive"))
      (node (ref "LED4") (pin "PAD_T") (pinfunction "PAD_PAD_T") (pintype "passive"))
      (node (ref "LED4") (pin "VIA1") (pinfunction "PAD_VIA1") (pintype "passive"))
      (node (ref "LED4") (pin "VIA10") (pinfunction "PAD_VIA10") (pintype "passive"))
      (node (ref "LED4") (pin "VIA11") (pinfunction "PAD_VIA11") (pintype "passive"))
      (node (ref "LED4") (pin "VIA12") (pinfunction "PAD_VIA12") (pintype "passive"))
      (node (ref "LED4") (pin "VIA2") (pinfunction "PAD_VIA2") (pintype "passive"))
      (node (ref "LED4") (pin "VIA3") (pinfunction "PAD_VIA3") (pintype "passive"))
      (node (ref "LED4") (pin "VIA4") (pinfunction "PAD_VIA4") (pintype "passive"))
      (node (ref "LED4") (pin "VIA5") (pinfunction "PAD_VIA5") (pintype "passive"))
      (node (ref "LED4") (pin "VIA6") (pinfunction "PAD_VIA6") (pintype "passive"))
      (node (ref "LED4") (pin "VIA7") (pinfunction "PAD_VIA7") (pintype "passive"))
      (node (ref "LED4") (pin "VIA8") (pinfunction "PAD_VIA8") (pintype "passive"))
      (node (ref "LED4") (pin "VIA9") (pinfunction "PAD_VIA9") (pintype "passive"))
      (node (ref "LED5") (pin "PAD_B") (pinfunction "PAD_PAD_B") (pintype "passive"))
      (node (ref "LED5") (pin "PAD_T") (pinfunction "PAD_PAD_T") (pintype "passive"))
      (node (ref "LED5") (pin "VIA1") (pinfunction "PAD_VIA1") (pintype "passive"))
      (node (ref "LED5") (pin "VIA10") (pinfunction "PAD_VIA10") (pintype "passive"))
      (node (ref "LED5") (pin "VIA11") (pinfunction "PAD_VIA11") (pintype "passive"))
      (node (ref "LED5") (pin "VIA12") (pinfunction "PAD_VIA12") (pintype "passive"))
      (node (ref "LED5") (pin "VIA2") (pinfunction "PAD_VIA2") (pintype "passive"))
      (node (ref "LED5") (pin "VIA3") (pinfunction "PAD_VIA3") (pintype "passive"))
      (node (ref "LED5") (pin "VIA4") (pinfunction "PAD_VIA4") (pintype "passive"))
      (node (ref "LED5") (pin "VIA5") (pinfunction "PAD_VIA5") (pintype "passive"))
      (node (ref "LED5") (pin "VIA6") (pinfunction "PAD_VIA6") (pintype "passive"))
      (node (ref "LED5") (pin "VIA7") (pinfunction "PAD_VIA7") (pintype "passive"))
      (node (ref "LED5") (pin "VIA8") (pinfunction "PAD_VIA8") (pintype "passive"))
      (node (ref "LED5") (pin "VIA9") (pinfunction "PAD_VIA9") (pintype "passive"))
      (node (ref "LED6") (pin "PAD_B") (pinfunction "PAD_PAD_B") (pintype "passive"))
      (node (ref "LED6") (pin "PAD_T") (pinfunction "PAD_PAD_T") (pintype "passive"))
      (node (ref "LED6") (pin "VIA1") (pinfunction "PAD_VIA1") (pintype "passive"))
      (node (ref "LED6") (pin "VIA10") (pinfunction "PAD_VIA10") (pintype "passive"))
      (node (ref "LED6") (pin "VIA11") (pinfunction "PAD_VIA11") (pintype "passive"))
      (node (ref "LED6") (pin "VIA12") (pinfunction "PAD_VIA12") (pintype "passive"))
      (node (ref "LED6") (pin "VIA2") (pinfunction "PAD_VIA2") (pintype "passive"))
      (node (ref "LED6") (pin "VIA3") (pinfunction "PAD_VIA3") (pintype "passive"))
      (node (ref "LED6") (pin "VIA4") (pinfunction "PAD_VIA4") (pintype "passive"))
      (node (ref "LED6") (pin "VIA5") (pinfunction "PAD_VIA5") (pintype "passive"))
      (node (ref "LED6") (pin "VIA6") (pinfunction "PAD_VIA6") (pintype "passive"))
      (node (ref "LED6") (pin "VIA7") (pinfunction "PAD_VIA7") (pintype "passive"))
      (node (ref "LED6") (pin "VIA8") (pinfunction "PAD_VIA8") (pintype "passive"))
      (node (ref "LED6") (pin "VIA9") (pinfunction "PAD_VIA9") (pintype "passive"))
      (node (ref "LED7") (pin "PAD_B") (pinfunction "PAD_PAD_B") (pintype "passive"))
      (node (ref "LED7") (pin "PAD_T") (pinfunction "PAD_PAD_T") (pintype "passive"))
      (node (ref "LED7") (pin "VIA1") (pinfunction "PAD_VIA1") (pintype "passive"))
      (node (ref "LED7") (pin "VIA10") (pinfunction "PAD_VIA10") (pintype "passive"))
      (node (ref "LED7") (pin "VIA11") (pinfunction "PAD_VIA11") (pintype "passive"))
      (node (ref "LED7") (pin "VIA12") (pinfunction "PAD_VIA12") (pintype "passive"))
      (node (ref "LED7") (pin "VIA2") (pinfunction "PAD_VIA2") (pintype "passive"))
      (node (ref "LED7") (pin "VIA3") (pinfunction "PAD_VIA3") (pintype "passive"))
      (node (ref "LED7") (pin "VIA4") (pinfunction "PAD_VIA4") (pintype "passive"))
      (node (ref "LED7") (pin "VIA5") (pinfunction "PAD_VIA5") (pintype "passive"))
      (node (ref "LED7") (pin "VIA6") (pinfunction "PAD_VIA6") (pintype "passive"))
      (node (ref "LED7") (pin "VIA7") (pinfunction "PAD_VIA7") (pintype "passive"))
      (node (ref "LED7") (pin "VIA8") (pinfunction "PAD_VIA8") (pintype "passive"))
      (node (ref "LED7") (pin "VIA9") (pinfunction "PAD_VIA9") (pintype "passive"))
      (node (ref "LED8") (pin "PAD_B") (pinfunction "PAD_PAD_B") (pintype "passive"))
      (node (ref "LED8") (pin "PAD_T") (pinfunction "PAD_PAD_T") (pintype "passive"))
      (node (ref "LED8") (pin "VIA1") (pinfunction "PAD_VIA1") (pintype "passive"))
      (node (ref "LED8") (pin "VIA10") (pinfunction "PAD_VIA10") (pintype "passive"))
      (node (ref "LED8") (pin "VIA11") (pinfunction "PAD_VIA11") (pintype "passive"))
      (node (ref "LED8") (pin "VIA12") (pinfunction "PAD_VIA12") (pintype "passive"))
      (node (ref "LED8") (pin "VIA2") (pinfunction "PAD_VIA2") (pintype "passive"))
      (node (ref "LED8") (pin "VIA3") (pinfunction "PAD_VIA3") (pintype "passive"))
      (node (ref "LED8") (pin "VIA4") (pinfunction "PAD_VIA4") (pintype "passive"))
      (node (ref "LED8") (pin "VIA5") (pinfunction "PAD_VIA5") (pintype "passive"))
      (node (ref "LED8") (pin "VIA6") (pinfunction "PAD_VIA6") (pintype "passive"))
      (node (ref "LED8") (pin "VIA7") (pinfunction "PAD_VIA7") (pintype "passive"))
      (node (ref "LED8") (pin "VIA8") (pinfunction "PAD_VIA8") (pintype "passive"))
      (node (ref "LED8") (pin "VIA9") (pinfunction "PAD_VIA9") (pintype "passive"))
      (node (ref "LED9") (pin "PAD_B") (pinfunction "PAD_PAD_B") (pintype "passive"))
      (node (ref "LED9") (pin "PAD_T") (pinfunction "PAD_PAD_T") (pintype "passive"))
      (node (ref "LED9") (pin "VIA1") (pinfunction "PAD_VIA1") (pintype "passive"))
      (node (ref "LED9") (pin "VIA10") (pinfunction "PAD_VIA10") (pintype "passive"))
      (node (ref "LED9") (pin "VIA11") (pinfunction "PAD_VIA11") (pintype "passive"))
      (node (ref "LED9") (pin "VIA12") (pinfunction "PAD_VIA12") (pintype "passive"))
      (node (ref "LED9") (pin "VIA2") (pinfunction "PAD_VIA2") (pintype "passive"))
      (node (ref "LED9") (pin "VIA3") (pinfunction "PAD_VIA3") (pintype "passive"))
      (node (ref "LED9") (pin "VIA4") (pinfunction "PAD_VIA4") (pintype "passive"))
      (node (ref "LED9") (pin "VIA5") (pinfunction "PAD_VIA5") (pintype "passive"))
      (node (ref "LED9") (pin "VIA6") (pinfunction "PAD_VIA6") (pintype "passive"))
      (node (ref "LED9") (pin "VIA7") (pinfunction "PAD_VIA7") (pintype "passive"))
      (node (ref "LED9") (pin "VIA8") (pinfunction "PAD_VIA8") (pintype "passive"))
      (node (ref "LED9") (pin "VIA9") (pinfunction "PAD_VIA9") (pintype "passive"))
    )
    (net (code "4") (name "GREEN") (class "Default")
      (node (ref "F3") (pin "2") (pinfunction "2_2") (pintype "passive"))
      (node (ref "J2") (pin "4") (pinfunction "4_4") (pintype "passive"))
      (node (ref "JP5") (pin "2") (pinfunction "2_2") (pintype "passive"))
      (node (ref "R6") (pin "2") (pinfunction "2_2") (pintype "passive"))
    )
    (net (code "5") (name "GREEN_BRG") (class "Default")
      (node (ref "JP4") (pin "1") (pinfunction "1_1") (pintype "passive"))
      (node (ref "R2") (pin "2") (pinfunction "2_2") (pintype "passive"))
    )
    (net (code "6") (name "GREEN_IN") (class "Default")
      (node (ref "D3") (pin "K") (pinfunction "K_K") (pintype "passive"))
      (node (ref "F3") (pin "1") (pinfunction "1_1") (pintype "passive"))
      (node (ref "J1") (pin "2") (pinfunction "2_2") (pintype "passive"))
    )
    (net (code "7") (name "Net-(JP4-Pad2)") (class "Default")
      (node (ref "JP4") (pin "2") (pinfunction "2_2") (pintype "passive"))
      (node (ref "JP5") (pin "1") (pinfunction "1_1") (pintype "passive"))
    )
    (net (code "8") (name "Net-(JP6-Pad2)") (class "Default")
      (node (ref "JP6") (pin "2") (pinfunction "2_2") (pintype "passive"))
      (node (ref "JP7") (pin "1") (pinfunction "1_1") (pintype "passive"))
    )
    (net (code "9") (name "Net-(JP7-Pad2)") (class "Default")
      (node (ref "JP7") (pin "2") (pinfunction "2_2") (pintype "passive"))
      (node (ref "JP8") (pin "1") (pinfunction "1_1") (pintype "passive"))
    )
    (net (code "10") (name "Net-(LED1-PadBLUE_P)") (class "Default")
      (node (ref "LED1") (pin "BLUE_P") (pinfunction "BLUE_P_BLUE_P") (pintype "input"))
      (node (ref "LED2") (pin "BLUE_N") (pinfunction "BLUE_N_BLUE_N") (pintype "output"))
    )
    (net (code "11") (name "Net-(LED1-PadGREEN_P)") (class "Default")
      (node (ref "LED1") (pin "GREEN_P") (pinfunction "GREEN_P_GREEN_P") (pintype "input"))
      (node (ref "LED2") (pin "GREEN_N") (pinfunction "GREEN_N_GREEN_N") (pintype "output"))
    )
    (net (code "12") (name "Net-(LED1-PadRED_P)") (class "Default")
      (node (ref "LED1") (pin "RED_P") (pinfunction "RED_P_RED_P") (pintype "input"))
      (node (ref "LED2") (pin "RED_N") (pinfunction "RED_N_RED_N") (pintype "output"))
    )
    (net (code "13") (name "Net-(LED1-PadWHITE_P)") (class "Default")
      (node (ref "LED1") (pin "WHITE_P") (pinfunction "WHITE_P_WHITE_P") (pintype "input"))
      (node (ref "LED2") (pin "WHITE_N") (pinfunction "WHITE_N_WHITE_N") (pintype "output"))
    )
    (net (code "14") (name "Net-(LED2-PadBLUE_P)") (class "Default")
      (node (ref "LED2") (pin "BLUE_P") (pinfunction "BLUE_P_BLUE_P") (pintype "input"))
      (node (ref "LED3") (pin "BLUE_N") (pinfunction "BLUE_N_BLUE_N") (pintype "output"))
    )
    (net (code "15") (name "Net-(LED2-PadGREEN_P)") (class "Default")
      (node (ref "LED2") (pin "GREEN_P") (pinfunction "GREEN_P_GREEN_P") (pintype "input"))
      (node (ref "LED3") (pin "GREEN_N") (pinfunction "GREEN_N_GREEN_N") (pintype "output"))
    )
    (net (code "16") (name "Net-(LED2-PadRED_P)") (class "Default")
      (node (ref "LED2") (pin "RED_P") (pinfunction "RED_P_RED_P") (pintype "input"))
      (node (ref "LED3") (pin "RED_N") (pinfunction "RED_N_RED_N") (pintype "output"))
    )
    (net (code "17") (name "Net-(LED2-PadWHITE_P)") (class "Default")
      (node (ref "LED2") (pin "WHITE_P") (pinfunction "WHITE_P_WHITE_P") (pintype "input"))
      (node (ref "LED3") (pin "WHITE_N") (pinfunction "WHITE_N_WHITE_N") (pintype "output"))
    )
    (net (code "18") (name "Net-(LED3-PadBLUE_P)") (class "Default")
      (node (ref "LED3") (pin "BLUE_P") (pinfunction "BLUE_P_BLUE_P") (pintype "input"))
      (node (ref "LED4") (pin "BLUE_N") (pinfunction "BLUE_N_BLUE_N") (pintype "output"))
    )
    (net (code "19") (name "Net-(LED3-PadGREEN_P)") (class "Default")
      (node (ref "LED3") (pin "GREEN_P") (pinfunction "GREEN_P_GREEN_P") (pintype "input"))
      (node (ref "LED4") (pin "GREEN_N") (pinfunction "GREEN_N_GREEN_N") (pintype "output"))
    )
    (net (code "20") (name "Net-(LED3-PadRED_P)") (class "Default")
      (node (ref "LED3") (pin "RED_P") (pinfunction "RED_P_RED_P") (pintype "input"))
      (node (ref "LED4") (pin "RED_N") (pinfunction "RED_N_RED_N") (pintype "output"))
    )
    (net (code "21") (name "Net-(LED3-PadWHITE_P)") (class "Default")
      (node (ref "LED3") (pin "WHITE_P") (pinfunction "WHITE_P_WHITE_P") (pintype "input"))
      (node (ref "LED4") (pin "WHITE_N") (pinfunction "WHITE_N_WHITE_N") (pintype "output"))
    )
    (net (code "22") (name "Net-(LED4-PadBLUE_P)") (class "Default")
      (node (ref "LED4") (pin "BLUE_P") (pinfunction "BLUE_P_BLUE_P") (pintype "input"))
      (node (ref "LED5") (pin "BLUE_N") (pinfunction "BLUE_N_BLUE_N") (pintype "output"))
    )
    (net (code "23") (name "Net-(LED4-PadGREEN_P)") (class "Default")
      (node (ref "LED4") (pin "GREEN_P") (pinfunction "GREEN_P_GREEN_P") (pintype "input"))
      (node (ref "LED5") (pin "GREEN_N") (pinfunction "GREEN_N_GREEN_N") (pintype "output"))
    )
    (net (code "24") (name "Net-(LED4-PadRED_P)") (class "Default")
      (node (ref "LED4") (pin "RED_P") (pinfunction "RED_P_RED_P") (pintype "input"))
      (node (ref "LED5") (pin "RED_N") (pinfunction "RED_N_RED_N") (pintype "output"))
    )
    (net (code "25") (name "Net-(LED4-PadWHITE_P)") (class "Default")
      (node (ref "LED4") (pin "WHITE_P") (pinfunction "WHITE_P_WHITE_P") (pintype "input"))
      (node (ref "LED5") (pin "WHITE_N") (pinfunction "WHITE_N_WHITE_N") (pintype "output"))
    )
    (net (code "26") (name "Net-(LED5-PadBLUE_P)") (class "Default")
      (node (ref "LED5") (pin "BLUE_P") (pinfunction "BLUE_P_BLUE_P") (pintype "input"))
      (node (ref "LED6") (pin "BLUE_N") (pinfunction "BLUE_N_BLUE_N") (pintype "output"))
    )
    (net (code "27") (name "Net-(LED5-PadGREEN_P)") (class "Default")
      (node (ref "LED5") (pin "GREEN_P") (pinfunction "GREEN_P_GREEN_P") (pintype "input"))
      (node (ref "LED6") (pin "GREEN_N") (pinfunction "GREEN_N_GREEN_N") (pintype "output"))
    )
    (net (code "28") (name "Net-(LED5-PadRED_P)") (class "Default")
      (node (ref "LED5") (pin "RED_P") (pinfunction "RED_P_RED_P") (pintype "input"))
      (node (ref "LED6") (pin "RED_N") (pinfunction "RED_N_RED_N") (pintype "output"))
    )
    (net (code "29") (name "Net-(LED5-PadWHITE_P)") (class "Default")
      (node (ref "LED5") (pin "WHITE_P") (pinfunction "WHITE_P_WHITE_P") (pintype "input"))
      (node (ref "LED6") (pin "WHITE_N") (pinfunction "WHITE_N_WHITE_N") (pintype "output"))
    )
    (net (code "30") (name "Net-(LED6-PadBLUE_P)") (class "Default")
      (node (ref "LED6") (pin "BLUE_P") (pinfunction "BLUE_P_BLUE_P") (pintype "input"))
      (node (ref "LED7") (pin "BLUE_N") (pinfunction "BLUE_N_BLUE_N") (pintype "output"))
    )
    (net (code "31") (name "Net-(LED6-PadGREEN_P)") (class "Default")
      (node (ref "LED6") (pin "GREEN_P") (pinfunction "GREEN_P_GREEN_P") (pintype "input"))
      (node (ref "LED7") (pin "GREEN_N") (pinfunction "GREEN_N_GREEN_N") (pintype "output"))
    )
    (net (code "32") (name "Net-(LED6-PadRED_P)") (class "Default")
      (node (ref "LED6") (pin "RED_P") (pinfunction "RED_P_RED_P") (pintype "input"))
      (node (ref "LED7") (pin "RED_N") (pinfunction "RED_N_RED_N") (pintype "output"))
    )
    (net (code "33") (name "Net-(LED6-PadWHITE_P)") (class "Default")
      (node (ref "LED6") (pin "WHITE_P") (pinfunction "WHITE_P_WHITE_P") (pintype "input"))
      (node (ref "LED7") (pin "WHITE_N") (pinfunction "WHITE_N_WHITE_N") (pintype "output"))
    )
    (net (code "34") (name "Net-(LED7-PadBLUE_P)") (class "Default")
      (node (ref "LED7") (pin "BLUE_P") (pinfunction "BLUE_P_BLUE_P") (pintype "input"))
      (node (ref "LED8") (pin "BLUE_N") (pinfunction "BLUE_N_BLUE_N") (pintype "output"))
    )
    (net (code "35") (name "Net-(LED7-PadGREEN_P)") (class "Default")
      (node (ref "LED7") (pin "GREEN_P") (pinfunction "GREEN_P_GREEN_P") (pintype "input"))
      (node (ref "LED8") (pin "GREEN_N") (pinfunction "GREEN_N_GREEN_N") (pintype "output"))
    )
    (net (code "36") (name "Net-(LED7-PadRED_P)") (class "Default")
      (node (ref "LED7") (pin "RED_P") (pinfunction "RED_P_RED_P") (pintype "input"))
      (node (ref "LED8") (pin "RED_N") (pinfunction "RED_N_RED_N") (pintype "output"))
    )
    (net (code "37") (name "Net-(LED7-PadWHITE_P)") (class "Default")
      (node (ref "LED7") (pin "WHITE_P") (pinfunction "WHITE_P_WHITE_P") (pintype "input"))
      (node (ref "LED8") (pin "WHITE_N") (pinfunction "WHITE_N_WHITE_N") (pintype "output"))
    )
    (net (code "38") (name "Net-(LED8-PadBLUE_P)") (class "Default")
      (node (ref "LED8") (pin "BLUE_P") (pinfunction "BLUE_P_BLUE_P") (pintype "input"))
      (node (ref "LED9") (pin "BLUE_N") (pinfunction "BLUE_N_BLUE_N") (pintype "output"))
    )
    (net (code "39") (name "Net-(LED8-PadGREEN_P)") (class "Default")
      (node (ref "LED8") (pin "GREEN_P") (pinfunction "GREEN_P_GREEN_P") (pintype "input"))
      (node (ref "LED9") (pin "GREEN_N") (pinfunction "GREEN_N_GREEN_N") (pintype "output"))
    )
    (net (code "40") (name "Net-(LED8-PadRED_P)") (class "Default")
      (node (ref "LED8") (pin "RED_P") (pinfunction "RED_P_RED_P") (pintype "input"))
      (node (ref "LED9") (pin "RED_N") (pinfunction "RED_N_RED_N") (pintype "output"))
    )
    (net (code "41") (name "Net-(LED8-PadWHITE_P)") (class "Default")
      (node (ref "LED8") (pin "WHITE_P") (pinfunction "WHITE_P_WHITE_P") (pintype "input"))
      (node (ref "LED9") (pin "WHITE_N") (pinfunction "WHITE_N_WHITE_N") (pintype "output"))
    )
    (net (code "42") (name "Net-(LED10-PadBLUE_N)") (class "Default")
      (node (ref "LED10") (pin "BLUE_N") (pinfunction "BLUE_N_BLUE_N") (pintype "output"))
      (node (ref "LED9") (pin "BLUE_P") (pinfunction "BLUE_P_BLUE_P") (pintype "input"))
    )
    (net (code "43") (name "Net-(LED10-PadBLUE_P)") (class "Default")
      (node (ref "LED10") (pin "BLUE_P") (pinfunction "BLUE_P_BLUE_P") (pintype "input"))
      (node (ref "LED11") (pin "BLUE_N") (pinfunction "BLUE_N_BLUE_N") (pintype "output"))
    )
    (net (code "44") (name "Net-(LED10-PadGREEN_N)") (class "Default")
      (node (ref "LED10") (pin "GREEN_N") (pinfunction "GREEN_N_GREEN_N") (pintype "output"))
      (node (ref "LED9") (pin "GREEN_P") (pinfunction "GREEN_P_GREEN_P") (pintype "input"))
    )
    (net (code "45") (name "Net-(LED10-PadGREEN_P)") (class "Default")
      (node (ref "LED10") (pin "GREEN_P") (pinfunction "GREEN_P_GREEN_P") (pintype "input"))
      (node (ref "LED11") (pin "GREEN_N") (pinfunction "GREEN_N_GREEN_N") (pintype "output"))
    )
    (net (code "46") (name "Net-(LED10-PadRED_N)") (class "Default")
      (node (ref "LED10") (pin "RED_N") (pinfunction "RED_N_RED_N") (pintype "output"))
      (node (ref "LED9") (pin "RED_P") (pinfunction "RED_P_RED_P") (pintype "input"))
    )
    (net (code "47") (name "Net-(LED10-PadRED_P)") (class "Default")
      (node (ref "LED10") (pin "RED_P") (pinfunction "RED_P_RED_P") (pintype "input"))
      (node (ref "LED11") (pin "RED_N") (pinfunction "RED_N_RED_N") (pintype "output"))
    )
    (net (code "48") (name "Net-(LED10-PadWHITE_N)") (class "Default")
      (node (ref "LED10") (pin "WHITE_N") (pinfunction "WHITE_N_WHITE_N") (pintype "output"))
      (node (ref "LED9") (pin "WHITE_P") (pinfunction "WHITE_P_WHITE_P") (pintype "input"))
    )
    (net (code "49") (name "Net-(LED10-PadWHITE_P)") (class "Default")
      (node (ref "LED10") (pin "WHITE_P") (pinfunction "WHITE_P_WHITE_P") (pintype "input"))
      (node (ref "LED11") (pin "WHITE_N") (pinfunction "WHITE_N_WHITE_N") (pintype "output"))
    )
    (net (code "50") (name "Net-(LED11-PadBLUE_P)") (class "Default")
      (node (ref "LED11") (pin "BLUE_P") (pinfunction "BLUE_P_BLUE_P") (pintype "input"))
      (node (ref "LED12") (pin "BLUE_N") (pinfunction "BLUE_N_BLUE_N") (pintype "output"))
    )
    (net (code "51") (name "Net-(LED11-PadGREEN_P)") (class "Default")
      (node (ref "LED11") (pin "GREEN_P") (pinfunction "GREEN_P_GREEN_P") (pintype "input"))
      (node (ref "LED12") (pin "GREEN_N") (pinfunction "GREEN_N_GREEN_N") (pintype "output"))
    )
    (net (code "52") (name "Net-(LED11-PadRED_P)") (class "Default")
      (node (ref "LED11") (pin "RED_P") (pinfunction "RED_P_RED_P") (pintype "input"))
      (node (ref "LED12") (pin "RED_N") (pinfunction "RED_N_RED_N") (pintype "output"))
    )
    (net (code "53") (name "Net-(LED11-PadWHITE_P)") (class "Default")
      (node (ref "LED11") (pin "WHITE_P") (pinfunction "WHITE_P_WHITE_P") (pintype "input"))
      (node (ref "LED12") (pin "WHITE_N") (pinfunction "WHITE_N_WHITE_N") (pintype "output"))
    )
    (net (code "54") (name "Net-(LED12-PadBLUE_P)") (class "Default")
      (node (ref "LED12") (pin "BLUE_P") (pinfunction "BLUE_P_BLUE_P") (pintype "input"))
      (node (ref "R3") (pin "1") (pinfunction "1_1") (pintype "passive"))
    )
    (net (code "55") (name "Net-(LED12-PadGREEN_P)") (class "Default")
      (node (ref "LED12") (pin "GREEN_P") (pinfunction "GREEN_P_GREEN_P") (pintype "input"))
      (node (ref "R2") (pin "1") (pinfunction "1_1") (pintype "passive"))
    )
    (net (code "56") (name "Net-(LED12-PadRED_P)") (class "Default")
      (node (ref "LED12") (pin "RED_P") (pinfunction "RED_P_RED_P") (pintype "input"))
      (node (ref "R1") (pin "1") (pinfunction "1_1") (pintype "passive"))
    )
    (net (code "57") (name "Net-(LED12-PadWHITE_P)") (class "Default")
      (node (ref "LED12") (pin "WHITE_P") (pinfunction "WHITE_P_WHITE_P") (pintype "input"))
      (node (ref "R4") (pin "1") (pinfunction "1_1") (pintype "passive"))
    )
    (net (code "58") (name "Net-(LED13-PadBLUE_P)") (class "Default")
      (node (ref "LED13") (pin "BLUE_P") (pinfunction "BLUE_P_BLUE_P") (pintype "input"))
      (node (ref "LED14") (pin "BLUE_N") (pinfunction "BLUE_N_BLUE_N") (pintype "output"))
    )
    (net (code "59") (name "Net-(LED13-PadGREEN_P)") (class "Default")
      (node (ref "LED13") (pin "GREEN_P") (pinfunction "GREEN_P_GREEN_P") (pintype "input"))
      (node (ref "LED14") (pin "GREEN_N") (pinfunction "GREEN_N_GREEN_N") (pintype "output"))
    )
    (net (code "60") (name "Net-(LED13-PadRED_P)") (class "Default")
      (node (ref "LED13") (pin "RED_P") (pinfunction "RED_P_RED_P") (pintype "input"))
      (node (ref "LED14") (pin "RED_N") (pinfunction "RED_N_RED_N") (pintype "output"))
    )
    (net (code "61") (name "Net-(LED13-PadWHITE_P)") (class "Default")
      (node (ref "LED13") (pin "WHITE_P") (pinfunction "WHITE_P_WHITE_P") (pintype "input"))
      (node (ref "LED14") (pin "WHITE_N") (pinfunction "WHITE_N_WHITE_N") (pintype "output"))
    )
    (net (code "62") (name "Net-(LED14-PadBLUE_P)") (class "Default")
      (node (ref "LED14") (pin "BLUE_P") (pinfunction "BLUE_P_BLUE_P") (pintype "input"))
      (node (ref "LED15") (pin "BLUE_N") (pinfunction "BLUE_N_BLUE_N") (pintype "output"))
    )
    (net (code "63") (name "Net-(LED14-PadGREEN_P)") (class "Default")
      (node (ref "LED14") (pin "GREEN_P") (pinfunction "GREEN_P_GREEN_P") (pintype "input"))
      (node (ref "LED15") (pin "GREEN_N") (pinfunction "GREEN_N_GREEN_N") (pintype "output"))
    )
    (net (code "64") (name "Net-(LED14-PadRED_P)") (class "Default")
      (node (ref "LED14") (pin "RED_P") (pinfunction "RED_P_RED_P") (pintype "input"))
      (node (ref "LED15") (pin "RED_N") (pinfunction "RED_N_RED_N") (pintype "output"))
    )
    (net (code "65") (name "Net-(LED14-PadWHITE_P)") (class "Default")
      (node (ref "LED14") (pin "WHITE_P") (pinfunction "WHITE_P_WHITE_P") (pintype "input"))
      (node (ref "LED15") (pin "WHITE_N") (pinfunction "WHITE_N_WHITE_N") (pintype "output"))
    )
    (net (code "66") (name "Net-(LED15-PadBLUE_P)") (class "Default")
      (node (ref "LED15") (pin "BLUE_P") (pinfunction "BLUE_P_BLUE_P") (pintype "input"))
      (node (ref "LED16") (pin "BLUE_N") (pinfunction "BLUE_N_BLUE_N") (pintype "output"))
    )
    (net (code "67") (name "Net-(LED15-PadGREEN_P)") (class "Default")
      (node (ref "LED15") (pin "GREEN_P") (pinfunction "GREEN_P_GREEN_P") (pintype "input"))
      (node (ref "LED16") (pin "GREEN_N") (pinfunction "GREEN_N_GREEN_N") (pintype "output"))
    )
    (net (code "68") (name "Net-(LED15-PadRED_P)") (class "Default")
      (node (ref "LED15") (pin "RED_P") (pinfunction "RED_P_RED_P") (pintype "input"))
      (node (ref "LED16") (pin "RED_N") (pinfunction "RED_N_RED_N") (pintype "output"))
    )
    (net (code "69") (name "Net-(LED15-PadWHITE_P)") (class "Default")
      (node (ref "LED15") (pin "WHITE_P") (pinfunction "WHITE_P_WHITE_P") (pintype "input"))
      (node (ref "LED16") (pin "WHITE_N") (pinfunction "WHITE_N_WHITE_N") (pintype "output"))
    )
    (net (code "70") (name "Net-(LED16-PadBLUE_P)") (class "Default")
      (node (ref "LED16") (pin "BLUE_P") (pinfunction "BLUE_P_BLUE_P") (pintype "input"))
      (node (ref "LED17") (pin "BLUE_N") (pinfunction "BLUE_N_BLUE_N") (pintype "output"))
    )
    (net (code "71") (name "Net-(LED16-PadGREEN_P)") (class "Default")
      (node (ref "LED16") (pin "GREEN_P") (pinfunction "GREEN_P_GREEN_P") (pintype "input"))
      (node (ref "LED17") (pin "GREEN_N") (pinfunction "GREEN_N_GREEN_N") (pintype "output"))
    )
    (net (code "72") (name "Net-(LED16-PadRED_P)") (class "Default")
      (node (ref "LED16") (pin "RED_P") (pinfunction "RED_P_RED_P") (pintype "input"))
      (node (ref "LED17") (pin "RED_N") (pinfunction "RED_N_RED_N") (pintype "output"))
    )
    (net (code "73") (name "Net-(LED16-PadWHITE_P)") (class "Default")
      (node (ref "LED16") (pin "WHITE_P") (pinfunction "WHITE_P_WHITE_P") (pintype "input"))
      (node (ref "LED17") (pin "WHITE_N") (pinfunction "WHITE_N_WHITE_N") (pintype "output"))
    )
    (net (code "74") (name "Net-(LED17-PadBLUE_P)") (class "Default")
      (node (ref "LED17") (pin "BLUE_P") (pinfunction "BLUE_P_BLUE_P") (pintype "input"))
      (node (ref "LED18") (pin "BLUE_N") (pinfunction "BLUE_N_BLUE_N") (pintype "output"))
    )
    (net (code "75") (name "Net-(LED17-PadGREEN_P)") (class "Default")
      (node (ref "LED17") (pin "GREEN_P") (pinfunction "GREEN_P_GREEN_P") (pintype "input"))
      (node (ref "LED18") (pin "GREEN_N") (pinfunction "GREEN_N_GREEN_N") (pintype "output"))
    )
    (net (code "76") (name "Net-(LED17-PadRED_P)") (class "Default")
      (node (ref "LED17") (pin "RED_P") (pinfunction "RED_P_RED_P") (pintype "input"))
      (node (ref "LED18") (pin "RED_N") (pinfunction "RED_N_RED_N") (pintype "output"))
    )
    (net (code "77") (name "Net-(LED17-PadWHITE_P)") (class "Default")
      (node (ref "LED17") (pin "WHITE_P") (pinfunction "WHITE_P_WHITE_P") (pintype "input"))
      (node (ref "LED18") (pin "WHITE_N") (pinfunction "WHITE_N_WHITE_N") (pintype "output"))
    )
    (net (code "78") (name "Net-(LED18-PadBLUE_P)") (class "Default")
      (node (ref "LED18") (pin "BLUE_P") (pinfunction "BLUE_P_BLUE_P") (pintype "input"))
      (node (ref "LED19") (pin "BLUE_N") (pinfunction "BLUE_N_BLUE_N") (pintype "output"))
    )
    (net (code "79") (name "Net-(LED18-PadGREEN_P)") (class "Default")
      (node (ref "LED18") (pin "GREEN_P") (pinfunction "GREEN_P_GREEN_P") (pintype "input"))
      (node (ref "LED19") (pin "GREEN_N") (pinfunction "GREEN_N_GREEN_N") (pintype "output"))
    )
    (net (code "80") (name "Net-(LED18-PadRED_P)") (class "Default")
      (node (ref "LED18") (pin "RED_P") (pinfunction "RED_P_RED_P") (pintype "input"))
      (node (ref "LED19") (pin "RED_N") (pinfunction "RED_N_RED_N") (pintype "output"))
    )
    (net (code "81") (name "Net-(LED18-PadWHITE_P)") (class "Default")
      (node (ref "LED18") (pin "WHITE_P") (pinfunction "WHITE_P_WHITE_P") (pintype "input"))
      (node (ref "LED19") (pin "WHITE_N") (pinfunction "WHITE_N_WHITE_N") (pintype "output"))
    )
    (net (code "82") (name "Net-(LED19-PadBLUE_P)") (class "Default")
      (node (ref "LED19") (pin "BLUE_P") (pinfunction "BLUE_P_BLUE_P") (pintype "input"))
      (node (ref "LED20") (pin "BLUE_N") (pinfunction "BLUE_N_BLUE_N") (pintype "output"))
    )
    (net (code "83") (name "Net-(LED19-PadGREEN_P)") (class "Default")
      (node (ref "LED19") (pin "GREEN_P") (pinfunction "GREEN_P_GREEN_P") (pintype "input"))
      (node (ref "LED20") (pin "GREEN_N") (pinfunction "GREEN_N_GREEN_N") (pintype "output"))
    )
    (net (code "84") (name "Net-(LED19-PadRED_P)") (class "Default")
      (node (ref "LED19") (pin "RED_P") (pinfunction "RED_P_RED_P") (pintype "input"))
      (node (ref "LED20") (pin "RED_N") (pinfunction "RED_N_RED_N") (pintype "output"))
    )
    (net (code "85") (name "Net-(LED19-PadWHITE_P)") (class "Default")
      (node (ref "LED19") (pin "WHITE_P") (pinfunction "WHITE_P_WHITE_P") (pintype "input"))
      (node (ref "LED20") (pin "WHITE_N") (pinfunction "WHITE_N_WHITE_N") (pintype "output"))
    )
    (net (code "86") (name "Net-(LED20-PadBLUE_P)") (class "Default")
      (node (ref "LED20") (pin "BLUE_P") (pinfunction "BLUE_P_BLUE_P") (pintype "input"))
      (node (ref "LED21") (pin "BLUE_N") (pinfunction "BLUE_N_BLUE_N") (pintype "output"))
    )
    (net (code "87") (name "Net-(LED20-PadGREEN_P)") (class "Default")
      (node (ref "LED20") (pin "GREEN_P") (pinfunction "GREEN_P_GREEN_P") (pintype "input"))
      (node (ref "LED21") (pin "GREEN_N") (pinfunction "GREEN_N_GREEN_N") (pintype "output"))
    )
    (net (code "88") (name "Net-(LED20-PadRED_P)") (class "Default")
      (node (ref "LED20") (pin "RED_P") (pinfunction "RED_P_RED_P") (pintype "input"))
      (node (ref "LED21") (pin "RED_N") (pinfunction "RED_N_RED_N") (pintype "output"))
    )
    (net (code "89") (name "Net-(LED20-PadWHITE_P)") (class "Default")
      (node (ref "LED20") (pin "WHITE_P") (pinfunction "WHITE_P_WHITE_P") (pintype "input"))
      (node (ref "LED21") (pin "WHITE_N") (pinfunction "WHITE_N_WHITE_N") (pintype "output"))
    )
    (net (code "90") (name "Net-(LED21-PadBLUE_P)") (class "Default")
      (node (ref "LED21") (pin "BLUE_P") (pinfunction "BLUE_P_BLUE_P") (pintype "input"))
      (node (ref "LED22") (pin "BLUE_N") (pinfunction "BLUE_N_BLUE_N") (pintype "output"))
    )
    (net (code "91") (name "Net-(LED21-PadGREEN_P)") (class "Default")
      (node (ref "LED21") (pin "GREEN_P") (pinfunction "GREEN_P_GREEN_P") (pintype "input"))
      (node (ref "LED22") (pin "GREEN_N") (pinfunction "GREEN_N_GREEN_N") (pintype "output"))
    )
    (net (code "92") (name "Net-(LED21-PadRED_P)") (class "Default")
      (node (ref "LED21") (pin "RED_P") (pinfunction "RED_P_RED_P") (pintype "input"))
      (node (ref "LED22") (pin "RED_N") (pinfunction "RED_N_RED_N") (pintype "output"))
    )
    (net (code "93") (name "Net-(LED21-PadWHITE_P)") (class "Default")
      (node (ref "LED21") (pin "WHITE_P") (pinfunction "WHITE_P_WHITE_P") (pintype "input"))
      (node (ref "LED22") (pin "WHITE_N") (pinfunction "WHITE_N_WHITE_N") (pintype "output"))
    )
    (net (code "94") (name "Net-(LED22-PadBLUE_P)") (class "Default")
      (node (ref "LED22") (pin "BLUE_P") (pinfunction "BLUE_P_BLUE_P") (pintype "input"))
      (node (ref "LED23") (pin "BLUE_N") (pinfunction "BLUE_N_BLUE_N") (pintype "output"))
    )
    (net (code "95") (name "Net-(LED22-PadGREEN_P)") (class "Default")
      (node (ref "LED22") (pin "GREEN_P") (pinfunction "GREEN_P_GREEN_P") (pintype "input"))
      (node (ref "LED23") (pin "GREEN_N") (pinfunction "GREEN_N_GREEN_N") (pintype "output"))
    )
    (net (code "96") (name "Net-(LED22-PadRED_P)") (class "Default")
      (node (ref "LED22") (pin "RED_P") (pinfunction "RED_P_RED_P") (pintype "input"))
      (node (ref "LED23") (pin "RED_N") (pinfunction "RED_N_RED_N") (pintype "output"))
    )
    (net (code "97") (name "Net-(LED22-PadWHITE_P)") (class "Default")
      (node (ref "LED22") (pin "WHITE_P") (pinfunction "WHITE_P_WHITE_P") (pintype "input"))
      (node (ref "LED23") (pin "WHITE_N") (pinfunction "WHITE_N_WHITE_N") (pintype "output"))
    )
    (net (code "98") (name "Net-(LED23-PadBLUE_P)") (class "Default")
      (node (ref "LED23") (pin "BLUE_P") (pinfunction "BLUE_P_BLUE_P") (pintype "input"))
      (node (ref "LED24") (pin "BLUE_N") (pinfunction "BLUE_N_BLUE_N") (pintype "output"))
    )
    (net (code "99") (name "Net-(LED23-PadGREEN_P)") (class "Default")
      (node (ref "LED23") (pin "GREEN_P") (pinfunction "GREEN_P_GREEN_P") (pintype "input"))
      (node (ref "LED24") (pin "GREEN_N") (pinfunction "GREEN_N_GREEN_N") (pintype "output"))
    )
    (net (code "100") (name "Net-(LED23-PadRED_P)") (class "Default")
      (node (ref "LED23") (pin "RED_P") (pinfunction "RED_P_RED_P") (pintype "input"))
      (node (ref "LED24") (pin "RED_N") (pinfunction "RED_N_RED_N") (pintype "output"))
    )
    (net (code "101") (name "Net-(LED23-PadWHITE_P)") (class "Default")
      (node (ref "LED23") (pin "WHITE_P") (pinfunction "WHITE_P_WHITE_P") (pintype "input"))
      (node (ref "LED24") (pin "WHITE_N") (pinfunction "WHITE_N_WHITE_N") (pintype "output"))
    )
    (net (code "102") (name "Net-(LED24-PadBLUE_P)") (class "Default")
      (node (ref "LED24") (pin "BLUE_P") (pinfunction "BLUE_P_BLUE_P") (pintype "input"))
      (node (ref "R7") (pin "1") (pinfunction "1_1") (pintype "passive"))
    )
    (net (code "103") (name "Net-(LED24-PadGREEN_P)") (class "Default")
      (node (ref "LED24") (pin "GREEN_P") (pinfunction "GREEN_P_GREEN_P") (pintype "input"))
      (node (ref "R6") (pin "1") (pinfunction "1_1") (pintype "passive"))
    )
    (net (code "104") (name "Net-(LED24-PadRED_P)") (class "Default")
      (node (ref "LED24") (pin "RED_P") (pinfunction "RED_P_RED_P") (pintype "input"))
      (node (ref "R5") (pin "1") (pinfunction "1_1") (pintype "passive"))
    )
    (net (code "105") (name "Net-(LED24-PadWHITE_P)") (class "Default")
      (node (ref "LED24") (pin "WHITE_P") (pinfunction "WHITE_P_WHITE_P") (pintype "input"))
      (node (ref "R8") (pin "1") (pinfunction "1_1") (pintype "passive"))
    )
    (net (code "106") (name "RED") (class "Default")
      (node (ref "F4") (pin "2") (pinfunction "2_2") (pintype "passive"))
      (node (ref "J2") (pin "5") (pinfunction "5_5") (pintype "passive"))
      (node (ref "JP8") (pin "2") (pinfunction "2_2") (pintype "passive"))
      (node (ref "R5") (pin "2") (pinfunction "2_2") (pintype "passive"))
    )
    (net (code "107") (name "RED_BRG") (class "Default")
      (node (ref "JP6") (pin "1") (pinfunction "1_1") (pintype "passive"))
      (node (ref "R1") (pin "2") (pinfunction "2_2") (pintype "passive"))
    )
    (net (code "108") (name "RED_IN") (class "Default")
      (node (ref "D4") (pin "K") (pinfunction "K_K") (pintype "passive"))
      (node (ref "F4") (pin "1") (pinfunction "1_1") (pintype "passive"))
      (node (ref "J1") (pin "1") (pinfunction "1_1") (pintype "passive"))
    )
    (net (code "109") (name "WHITE") (class "Default")
      (node (ref "F2") (pin "2") (pinfunction "2_2") (pintype "passive"))
      (node (ref "J2") (pin "3") (pinfunction "3_3") (pintype "passive"))
      (node (ref "JP3") (pin "2") (pinfunction "2_2") (pintype "passive"))
      (node (ref "R8") (pin "2") (pinfunction "2_2") (pintype "passive"))
    )
    (net (code "110") (name "WHITE_BRG") (class "Default")
      (node (ref "JP3") (pin "1") (pinfunction "1_1") (pintype "passive"))
      (node (ref "R4") (pin "2") (pinfunction "2_2") (pintype "passive"))
    )
    (net (code "111") (name "WHITE_IN") (class "Default")
      (node (ref "D2") (pin "K") (pinfunction "K_K") (pintype "passive"))
      (node (ref "F2") (pin "1") (pinfunction "1_1") (pintype "passive"))
      (node (ref "J1") (pin "3") (pinfunction "3_3") (pintype "passive"))
    )
  )
)
